# controlStepperMotor.net
KiCad netlist of a schematic drawn in EAGLE
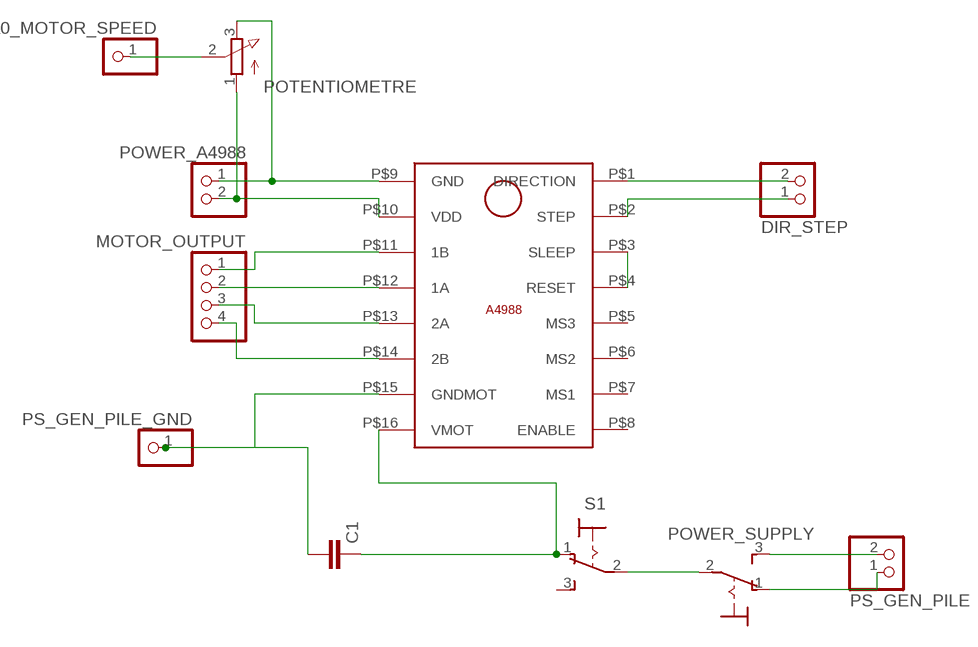
[diagram p0: schematic, sheet 1]

(export (version "E")
  (design (tool "Eeschema 10.0.6"))
  (components
    (comp (ref "A0_MOTOR_SPEED")
      (value "PINHD-1X1")
      (footprint "eagle-import:1X01")
      (libsource (lib "eagle-import") (part "PINHD-1X1"))
    )
    (comp (ref "C1")
      (value "C2,5-3")
      (footprint "eagle-import:C2.5-3")
      (libsource (lib "eagle-import") (part "C2,5-3"))
    )
    (comp (ref "DIR_STEP")
      (value "PINHD-1X2")
      (footprint "eagle-import:1X02")
      (libsource (lib "eagle-import") (part "PINHD-1X2"))
    )
    (comp (ref "MOTOR_OUTPUT")
      (value "PINHD-1X4")
      (footprint "eagle-import:1X04")
      (libsource (lib "eagle-import") (part "PINHD-1X4"))
    )
    (comp (ref "POTENTIOMETRE")
      (value "3RP/1610N")
      (footprint "eagle-import:3RP_1610N")
      (libsource (lib "eagle-import") (part "3RP/1610N"))
    )
    (comp (ref "POWER_A4988")
      (value "PINHD-1X2")
      (footprint "eagle-import:1X02")
      (libsource (lib "eagle-import") (part "PINHD-1X2"))
    )
    (comp (ref "POWER_SUPPLY")
      (value "320-916")
      (footprint "eagle-import:320-916")
      (libsource (lib "eagle-import") (part "320-916"))
    )
    (comp (ref "PS_GEN_PILE")
      (value "PINHD-1X2")
      (footprint "eagle-import:1X02")
      (libsource (lib "eagle-import") (part "PINHD-1X2"))
    )
    (comp (ref "PS_GEN_PILE_GND")
      (value "PINHD-1X1")
      (footprint "eagle-import:1X01")
      (libsource (lib "eagle-import") (part "PINHD-1X1"))
    )
    (comp (ref "S1")
      (value "M9040P")
      (footprint "eagle-import:M9040P")
      (libsource (lib "eagle-import") (part "M9040P"))
    )
    (comp (ref "U$1")
      (value "A4988-DRIVER-MOTOR")
      (footprint "eagle-import:A4988-DRIVER-MOTOR")
      (libsource (lib "eagle-import") (part "A4988-DRIVER-MOTOR"))
    )
  )
  (nets
    (net (code "1") (name "Net-(POTENTIOMETRE-A)") (class "Default")
      (node (ref "POTENTIOMETRE") (pin "1") (pinfunction "A_1") (pintype "passive"))
      (node (ref "POWER_A4988") (pin "2") (pinfunction "2_2") (pintype "passive"))
      (node (ref "U$1") (pin "P$10") (pinfunction "VDD_P$10") (pintype "bidirectional"))
    )
    (net (code "2") (name "Net-(POTENTIOMETRE-E)") (class "Default")
      (node (ref "POTENTIOMETRE") (pin "3") (pinfunction "E_3") (pintype "passive"))
      (node (ref "POWER_A4988") (pin "1") (pinfunction "1_1") (pintype "passive"))
      (node (ref "U$1") (pin "P$9") (pinfunction "GND_P$9") (pintype "bidirectional"))
    )
    (net (code "3") (name "Net-(POTENTIOMETRE-S)") (class "Default")
      (node (ref "A0_MOTOR_SPEED") (pin "1") (pinfunction "1_1") (pintype "passive"))
      (node (ref "POTENTIOMETRE") (pin "2") (pinfunction "S_2") (pintype "passive"))
    )
    (net (code "4") (name "Net-(POWER_SUPPLY-O)") (class "Default")
      (node (ref "POWER_SUPPLY") (pin "1") (pinfunction "O_1") (pintype "passive"))
      (node (ref "PS_GEN_PILE") (pin "1") (pinfunction "1_1") (pintype "passive"))
    )
    (net (code "5") (name "Net-(POWER_SUPPLY-P)") (class "Default")
      (node (ref "POWER_SUPPLY") (pin "2") (pinfunction "P_2") (pintype "passive"))
      (node (ref "S1") (pin "2") (pinfunction "P_2") (pintype "passive"))
    )
    (net (code "6") (name "Net-(POWER_SUPPLY-S)") (class "Default")
      (node (ref "POWER_SUPPLY") (pin "3") (pinfunction "S_3") (pintype "passive"))
      (node (ref "PS_GEN_PILE") (pin "2") (pinfunction "2_2") (pintype "passive"))
    )
    (net (code "7") (name "Net-(S1-O)") (class "Default")
      (node (ref "C1") (pin "1") (pinfunction "1_1") (pintype "passive"))
      (node (ref "S1") (pin "1") (pinfunction "O_1") (pintype "passive"))
      (node (ref "U$1") (pin "P$16") (pinfunction "VMOT_P$16") (pintype "bidirectional"))
    )
    (net (code "8") (name "Net-(U$1-1A)") (class "Default")
      (node (ref "MOTOR_OUTPUT") (pin "2") (pinfunction "2_2") (pintype "passive"))
      (node (ref "U$1") (pin "P$12") (pinfunction "1A_P$12") (pintype "bidirectional"))
    )
    (net (code "9") (name "Net-(U$1-1B)") (class "Default")
      (node (ref "MOTOR_OUTPUT") (pin "1") (pinfunction "1_1") (pintype "passive"))
      (node (ref "U$1") (pin "P$11") (pinfunction "1B_P$11") (pintype "bidirectional"))
    )
    (net (code "10") (name "Net-(U$1-2A)") (class "Default")
      (node (ref "MOTOR_OUTPUT") (pin "3") (pinfunction "3_3") (pintype "passive"))
      (node (ref "U$1") (pin "P$13") (pinfunction "2A_P$13") (pintype "bidirectional"))
    )
    (net (code "11") (name "Net-(U$1-2B)") (class "Default")
      (node (ref "MOTOR_OUTPUT") (pin "4") (pinfunction "4_4") (pintype "passive"))
      (node (ref "U$1") (pin "P$14") (pinfunction "2B_P$14") (pintype "bidirectional"))
    )
    (net (code "12") (name "Net-(U$1-DIRECTION)") (class "Default")
      (node (ref "DIR_STEP") (pin "2") (pinfunction "2_2") (pintype "passive"))
      (node (ref "U$1") (pin "P$1") (pinfunction "DIRECTION_P$1") (pintype "bidirectional"))
    )
    (net (code "13") (name "Net-(U$1-GNDMOT)") (class "Default")
      (node (ref "C1") (pin "2") (pinfunction "2_2") (pintype "passive"))
      (node (ref "PS_GEN_PILE_GND") (pin "1") (pinfunction "1_1") (pintype "passive"))
      (node (ref "U$1") (pin "P$15") (pinfunction "GNDMOT_P$15") (pintype "bidirectional"))
    )
    (net (code "14") (name "Net-(U$1-STEP)") (class "Default")
      (node (ref "DIR_STEP") (pin "1") (pinfunction "1_1") (pintype "passive"))
      (node (ref "U$1") (pin "P$2") (pinfunction "STEP_P$2") (pintype "bidirectional"))
    )
    (net (code "15") (name "unconnected-(S1-S-Pad3)") (class "Default")
      (node (ref "S1") (pin "3") (pinfunction "S_3") (pintype "passive"))
    )
    (net (code "16") (name "unconnected-(U$1-ENABLE-PadP$8)") (class "Default")
      (node (ref "U$1") (pin "P$8") (pinfunction "ENABLE_P$8") (pintype "bidirectional"))
    )
    (net (code "17") (name "unconnected-(U$1-MS1-PadP$7)") (class "Default")
      (node (ref "U$1") (pin "P$7") (pinfunction "MS1_P$7") (pintype "bidirectional"))
    )
    (net (code "18") (name "unconnected-(U$1-MS2-PadP$6)") (class "Default")
      (node (ref "U$1") (pin "P$6") (pinfunction "MS2_P$6") (pintype "bidirectional"))
    )
    (net (code "19") (name "unconnected-(U$1-MS3-PadP$5)") (class "Default")
      (node (ref "U$1") (pin "P$5") (pinfunction "MS3_P$5") (pintype "bidirectional"))
    )
    (net (code "20") (name "unconnected-(U$1-RESET-PadP$4)") (class "Default")
      (node (ref "U$1") (pin "P$4") (pinfunction "RESET_P$4") (pintype "bidirectional"))
    )
    (net (code "21") (name "unconnected-(U$1-SLEEP-PadP$3)") (class "Default")
      (node (ref "U$1") (pin "P$3") (pinfunction "SLEEP_P$3") (pintype "bidirectional"))
    )
  )
)
